# EntradasAnalogicas.net
KiCad netlist of a schematic drawn in Altium Designer
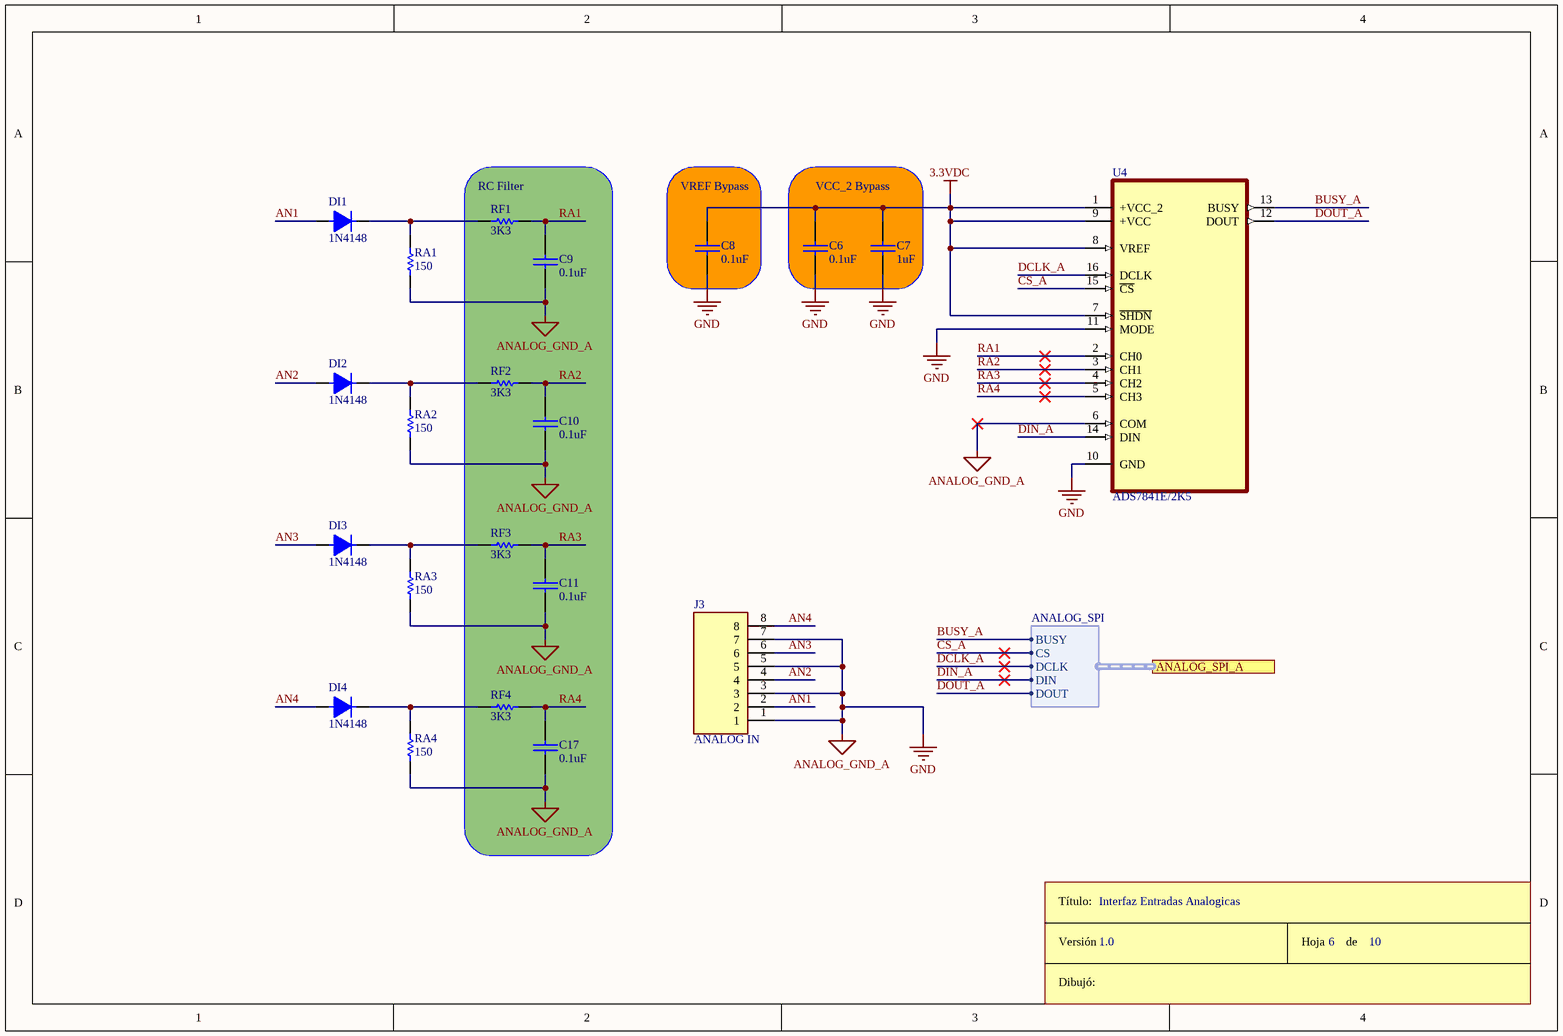
[diagram p0: EntradasAnalogicas.SchDoc]

(export (version "E")
  (design (tool "Eeschema 10.0.6"))
  (components
    (comp (ref "C6") (value "0.1uF") (footprint "CAP100") (libsource (lib "LIBEBAL") (part "CAP")))
    (comp (ref "C7") (value "1uF") (footprint "CAP100") (libsource (lib "LIBEBAL") (part "CAP")))
    (comp (ref "C8") (value "0.1uF") (footprint "CAP100") (libsource (lib "LIBEBAL") (part "CAP")))
    (comp (ref "C9") (value "0.1uF") (footprint "CAP100") (libsource (lib "LIBEBAL") (part "CAP")))
    (comp (ref "C10") (value "0.1uF") (footprint "CAP100") (libsource (lib "LIBEBAL") (part "CAP")))
    (comp (ref "C11") (value "0.1uF") (footprint "CAP100") (libsource (lib "LIBEBAL") (part "CAP")))
    (comp (ref "C17") (value "0.1uF") (footprint "CAP100") (libsource (lib "LIBEBAL") (part "CAP")))
    (comp (ref "DI1") (value "1N4148") (footprint "DO41") (libsource (lib "LIBEBAL") (part "DIODO")))
    (comp (ref "DI2") (value "1N4148") (footprint "DO41") (libsource (lib "LIBEBAL") (part "DIODO")))
    (comp (ref "DI3") (value "1N4148") (footprint "DO41") (libsource (lib "LIBEBAL") (part "DIODO")))
    (comp (ref "DI4") (value "1N4148") (footprint "DO41") (libsource (lib "LIBEBAL") (part "DIODO")))
    (comp (ref "J3")
      (value "ANALOG IN")
      (footprint "TE_1586863-8")
      (description "Conn Power HDR 8 POS 4.2mm Solder RA Thru-Hole 8 Terminal 1 Port Tray")
      (fields (field (name "MF") "TE Connectivity") (field (name "MP") "1586863-8"))
      (libsource (lib "MFW8R") (part "1586863-8"))
    )
    (comp (ref "RA1") (value "150") (footprint "RES300") (libsource (lib "LIBEBAL") (part "RES")))
    (comp (ref "RA2") (value "150") (footprint "RES300") (libsource (lib "LIBEBAL") (part "RES")))
    (comp (ref "RA3") (value "150") (footprint "RES300") (libsource (lib "LIBEBAL") (part "RES")))
    (comp (ref "RA4") (value "150") (footprint "RES300") (libsource (lib "LIBEBAL") (part "RES")))
    (comp (ref "RF1") (value "3K3") (footprint "RES300") (libsource (lib "LIBEBAL") (part "RES")))
    (comp (ref "RF2") (value "3K3") (footprint "RES300") (libsource (lib "LIBEBAL") (part "RES")))
    (comp (ref "RF3") (value "3K3") (footprint "RES300") (libsource (lib "LIBEBAL") (part "RES")))
    (comp (ref "RF4") (value "3K3") (footprint "RES300") (libsource (lib "LIBEBAL") (part "RES")))
    (comp (ref "ROT4") (value "Rótulo") (libsource (lib "LIB PIO IX") (part "Rótulo")))
    (comp (ref "U4")
      (value "ADS7841E/2K5")
      (footprint "SOP63P600X175-16N")
      (description "ANALOG-TO-DIGITAL CONVERTER")
      (libsource (lib "ADS7841E_2K5_Rev2") (part "ADS7841E/2K5"))
    )
  )
  (nets
    (net (code "2") (name "/AN1") (class "Default")
      (node (ref "DI1") (pin "1") (pinfunction "1_1") (pintype "passive"))
      (node (ref "J3") (pin "2") (pinfunction "2_2") (pintype "passive"))
    )
    (net (code "3") (name "/AN2") (class "Default")
      (node (ref "DI2") (pin "1") (pinfunction "1_1") (pintype "passive"))
      (node (ref "J3") (pin "4") (pinfunction "4_4") (pintype "passive"))
    )
    (net (code "4") (name "/AN3") (class "Default")
      (node (ref "DI3") (pin "1") (pinfunction "1_1") (pintype "passive"))
      (node (ref "J3") (pin "6") (pinfunction "6_6") (pintype "passive"))
    )
    (net (code "5") (name "/AN4") (class "Default")
      (node (ref "DI4") (pin "1") (pinfunction "1_1") (pintype "passive"))
      (node (ref "J3") (pin "8") (pinfunction "8_8") (pintype "passive"))
    )
    (net (code "6") (name "/BUSY_A") (class "Default")
      (node (ref "U4") (pin "13") (pinfunction "BUSY_13") (pintype "output"))
    )
    (net (code "7") (name "/CS_A") (class "Default")
      (node (ref "U4") (pin "15") (pinfunction "~{CS}_15") (pintype "input"))
    )
    (net (code "8") (name "/DCLK_A") (class "Default")
      (node (ref "U4") (pin "16") (pinfunction "DCLK_16") (pintype "input"))
    )
    (net (code "9") (name "/DIN_A") (class "Default")
      (node (ref "U4") (pin "14") (pinfunction "DIN_14") (pintype "input"))
    )
    (net (code "10") (name "/DOUT_A") (class "Default")
      (node (ref "U4") (pin "12") (pinfunction "DOUT_12") (pintype "output"))
    )
    (net (code "11") (name "/RA1") (class "Default")
      (node (ref "C9") (pin "1") (pinfunction "1_1") (pintype "passive"))
      (node (ref "RF1") (pin "2") (pinfunction "2_2") (pintype "passive"))
      (node (ref "U4") (pin "2") (pinfunction "CH0_2") (pintype "input"))
    )
    (net (code "12") (name "/RA2") (class "Default")
      (node (ref "C10") (pin "1") (pinfunction "1_1") (pintype "passive"))
      (node (ref "RF2") (pin "2") (pinfunction "2_2") (pintype "passive"))
      (node (ref "U4") (pin "3") (pinfunction "CH1_3") (pintype "input"))
    )
    (net (code "13") (name "/RA3") (class "Default")
      (node (ref "C11") (pin "1") (pinfunction "1_1") (pintype "passive"))
      (node (ref "RF3") (pin "2") (pinfunction "2_2") (pintype "passive"))
      (node (ref "U4") (pin "4") (pinfunction "CH2_4") (pintype "input"))
    )
    (net (code "14") (name "/RA4") (class "Default")
      (node (ref "C17") (pin "1") (pinfunction "1_1") (pintype "passive"))
      (node (ref "RF4") (pin "2") (pinfunction "2_2") (pintype "passive"))
      (node (ref "U4") (pin "5") (pinfunction "CH3_5") (pintype "input"))
    )
    (net (code "16") (name "3.3VDC") (class "Default")
      (node (ref "C6") (pin "1") (pinfunction "1_1") (pintype "passive"))
      (node (ref "C7") (pin "1") (pinfunction "1_1") (pintype "passive"))
      (node (ref "C8") (pin "1") (pinfunction "1_1") (pintype "passive"))
      (node (ref "U4") (pin "1") (pinfunction "+VCC_2_1") (pintype "power_in"))
      (node (ref "U4") (pin "7") (pinfunction "~{SHDN}_7") (pintype "input"))
      (node (ref "U4") (pin "8") (pinfunction "VREF_8") (pintype "input"))
      (node (ref "U4") (pin "9") (pinfunction "+VCC_9") (pintype "power_in"))
    )
    (net (code "17") (name "ANALOG_GND_A") (class "Default")
      (node (ref "C10") (pin "2") (pinfunction "2_2") (pintype "passive"))
      (node (ref "C11") (pin "2") (pinfunction "2_2") (pintype "passive"))
      (node (ref "C17") (pin "2") (pinfunction "2_2") (pintype "passive"))
      (node (ref "C6") (pin "2") (pinfunction "2_2") (pintype "passive"))
      (node (ref "C7") (pin "2") (pinfunction "2_2") (pintype "passive"))
      (node (ref "C8") (pin "2") (pinfunction "2_2") (pintype "passive"))
      (node (ref "C9") (pin "2") (pinfunction "2_2") (pintype "passive"))
      (node (ref "J3") (pin "1") (pinfunction "1_1") (pintype "passive"))
      (node (ref "J3") (pin "3") (pinfunction "3_3") (pintype "passive"))
      (node (ref "J3") (pin "5") (pinfunction "5_5") (pintype "passive"))
      (node (ref "J3") (pin "7") (pinfunction "7_7") (pintype "passive"))
      (node (ref "RA1") (pin "1") (pinfunction "1_1") (pintype "passive"))
      (node (ref "RA2") (pin "1") (pinfunction "1_1") (pintype "passive"))
      (node (ref "RA3") (pin "1") (pinfunction "1_1") (pintype "passive"))
      (node (ref "RA4") (pin "1") (pinfunction "1_1") (pintype "passive"))
      (node (ref "U4") (pin "10") (pinfunction "GND_10") (pintype "passive"))
      (node (ref "U4") (pin "11") (pinfunction "MODE_11") (pintype "input"))
      (node (ref "U4") (pin "6") (pinfunction "COM_6") (pintype "input"))
    )
    (net (code "18") (name "Net-(DI1-Pad2)") (class "Default")
      (node (ref "DI1") (pin "2") (pinfunction "2_2") (pintype "passive"))
      (node (ref "RA1") (pin "2") (pinfunction "2_2") (pintype "passive"))
      (node (ref "RF1") (pin "1") (pinfunction "1_1") (pintype "passive"))
    )
    (net (code "19") (name "Net-(DI2-Pad2)") (class "Default")
      (node (ref "DI2") (pin "2") (pinfunction "2_2") (pintype "passive"))
      (node (ref "RA2") (pin "2") (pinfunction "2_2") (pintype "passive"))
      (node (ref "RF2") (pin "1") (pinfunction "1_1") (pintype "passive"))
    )
    (net (code "20") (name "Net-(DI3-Pad2)") (class "Default")
      (node (ref "DI3") (pin "2") (pinfunction "2_2") (pintype "passive"))
      (node (ref "RA3") (pin "2") (pinfunction "2_2") (pintype "passive"))
      (node (ref "RF3") (pin "1") (pinfunction "1_1") (pintype "passive"))
    )
    (net (code "21") (name "Net-(DI4-Pad2)") (class "Default")
      (node (ref "DI4") (pin "2") (pinfunction "2_2") (pintype "passive"))
      (node (ref "RA4") (pin "2") (pinfunction "2_2") (pintype "passive"))
      (node (ref "RF4") (pin "1") (pinfunction "1_1") (pintype "passive"))
    )
  )
)
